# 2PLUS_Osc_Breakout_Euro.net
KiCad netlist of a schematic drawn in EAGLE
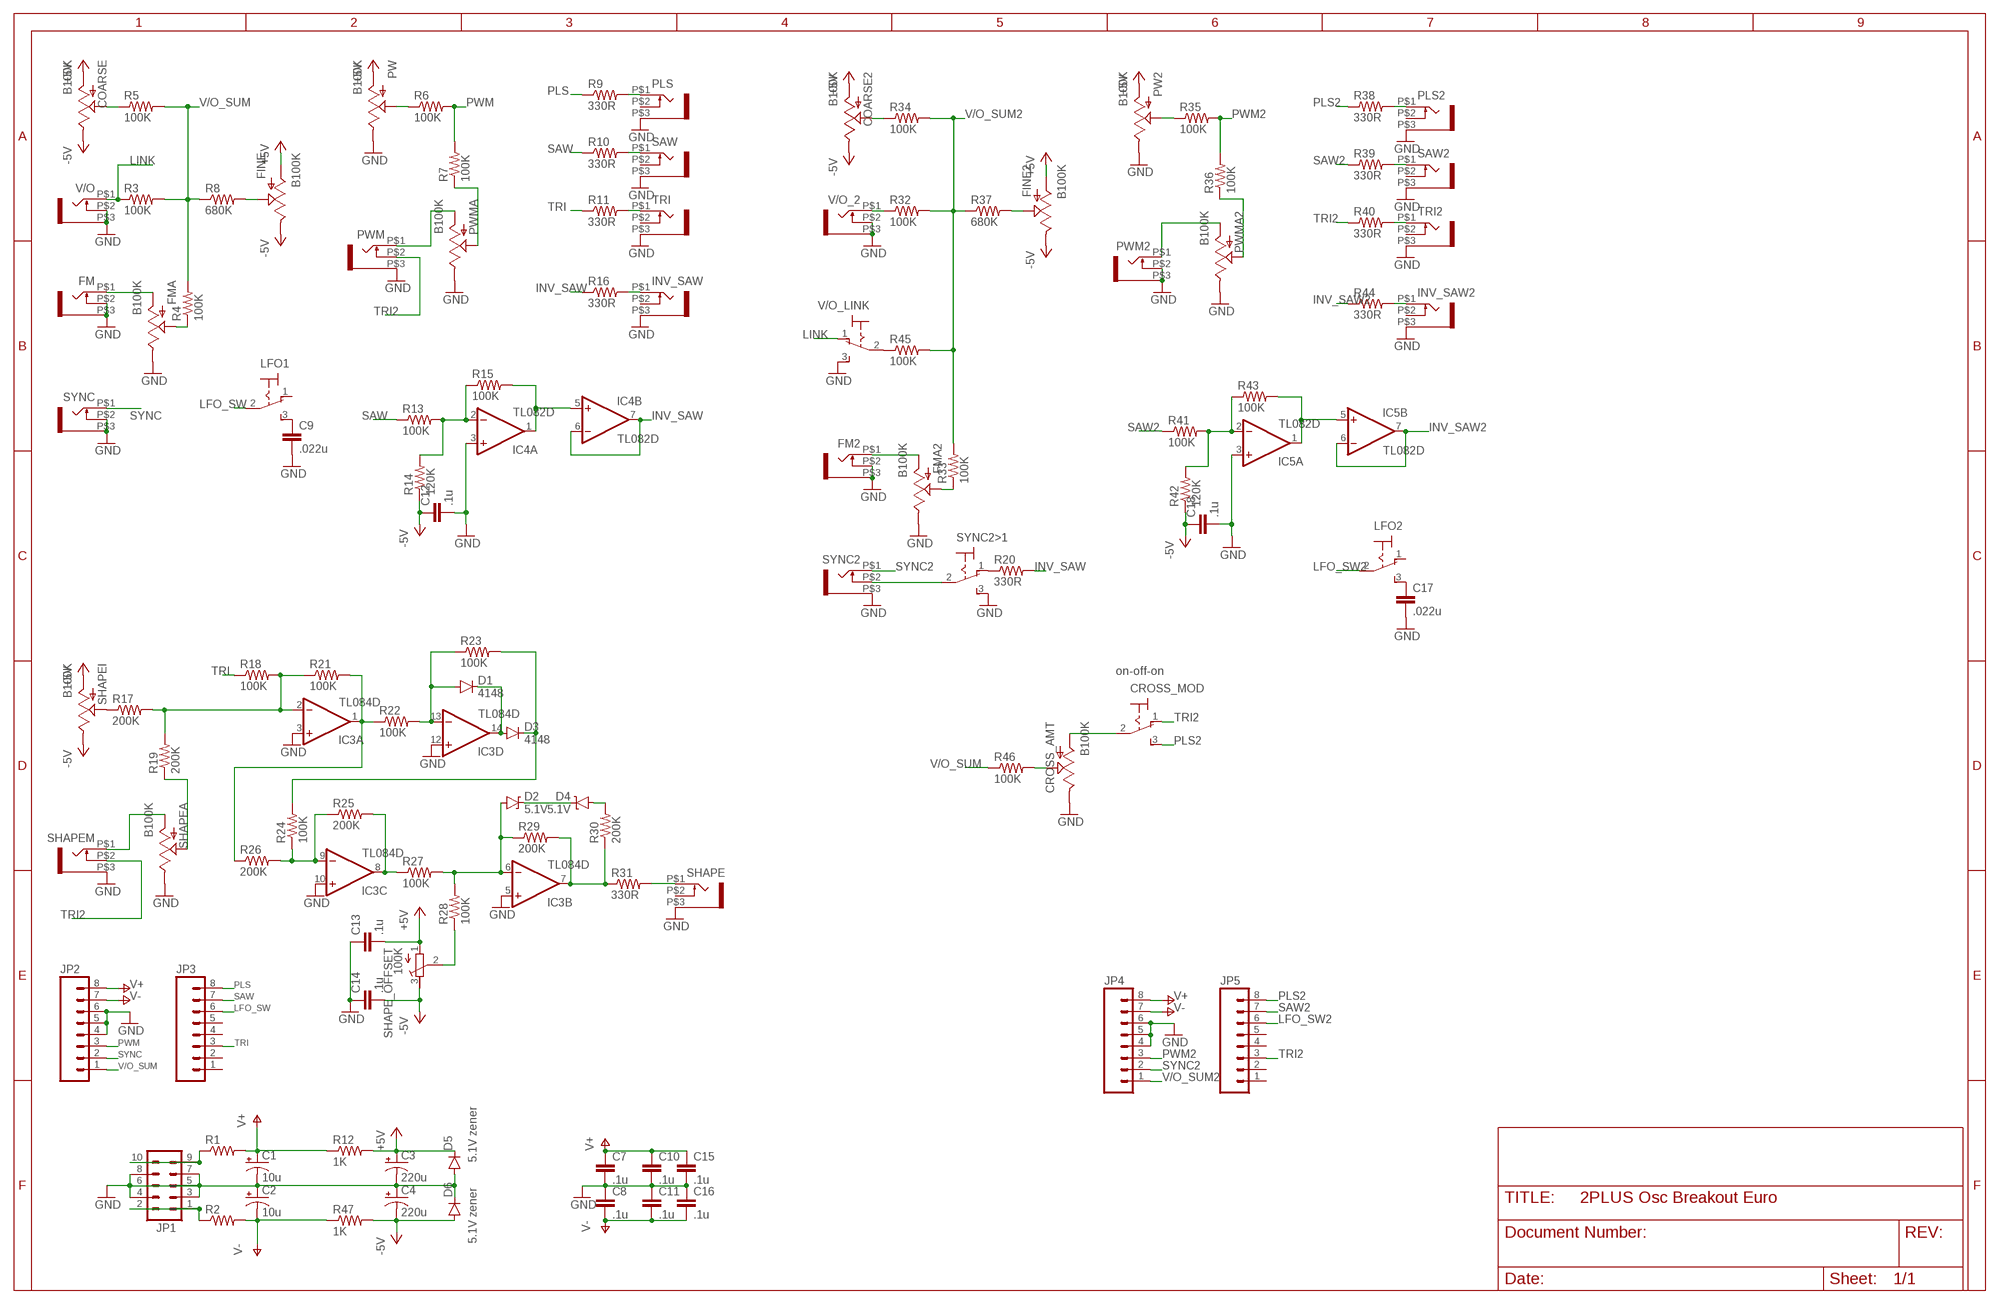
[diagram p0: schematic, sheet 1]

(export (version "E")
  (design (tool "Eeschema 10.0.6"))
  (components
    (comp (ref "C1")
      (value "10u")
      (footprint "eagle-import:PANASONIC_C")
      (libsource (lib "eagle-import") (part "CAP_POLC"))
    )
    (comp (ref "C2")
      (value "10u")
      (footprint "eagle-import:PANASONIC_C")
      (libsource (lib "eagle-import") (part "CAP_POLC"))
    )
    (comp (ref "C3")
      (value "220u")
      (footprint "eagle-import:E2,5-5")
      (libsource (lib "eagle-import") (part "CPOL-USE2.5-5"))
    )
    (comp (ref "C4")
      (value "220u")
      (footprint "eagle-import:E2,5-5")
      (libsource (lib "eagle-import") (part "CPOL-USE2.5-5"))
    )
    (comp (ref "C7")
      (value ".1u")
      (footprint "eagle-import:0805")
      (libsource (lib "eagle-import") (part "CAP0805"))
    )
    (comp (ref "C8")
      (value ".1u")
      (footprint "eagle-import:0805")
      (libsource (lib "eagle-import") (part "CAP0805"))
    )
    (comp (ref "C9")
      (value ".022u")
      (footprint "eagle-import:0805")
      (libsource (lib "eagle-import") (part "CAP0805"))
    )
    (comp (ref "C10")
      (value ".1u")
      (footprint "eagle-import:0805")
      (libsource (lib "eagle-import") (part "CAP0805"))
    )
    (comp (ref "C11")
      (value ".1u")
      (footprint "eagle-import:0805")
      (libsource (lib "eagle-import") (part "CAP0805"))
    )
    (comp (ref "C12")
      (value ".1u")
      (footprint "eagle-import:0805")
      (libsource (lib "eagle-import") (part "CAP0805"))
    )
    (comp (ref "C13")
      (value ".1u")
      (footprint "eagle-import:0805")
      (libsource (lib "eagle-import") (part "CAP0805"))
    )
    (comp (ref "C14")
      (value ".1u")
      (footprint "eagle-import:0805")
      (libsource (lib "eagle-import") (part "CAP0805"))
    )
    (comp (ref "C15")
      (value ".1u")
      (footprint "eagle-import:0805")
      (libsource (lib "eagle-import") (part "CAP0805"))
    )
    (comp (ref "C16")
      (value ".1u")
      (footprint "eagle-import:0805")
      (libsource (lib "eagle-import") (part "CAP0805"))
    )
    (comp (ref "C17")
      (value ".022u")
      (footprint "eagle-import:0805")
      (libsource (lib "eagle-import") (part "CAP0805"))
    )
    (comp (ref "C18")
      (value ".1u")
      (footprint "eagle-import:0805")
      (libsource (lib "eagle-import") (part "CAP0805"))
    )
    (comp (ref "COARSE")
      (value "B100K")
      (footprint "eagle-import:ALPS_POT")
      (libsource (lib "eagle-import") (part "POT"))
    )
    (comp (ref "COARSE2")
      (value "B100K")
      (footprint "eagle-import:ALPS_POT")
      (libsource (lib "eagle-import") (part "POT"))
    )
    (comp (ref "CROSS_AMT")
      (value "B100K")
      (footprint "eagle-import:ALPS_POT")
      (libsource (lib "eagle-import") (part "POT"))
    )
    (comp (ref "CROSS_MOD")
      (value "M9040P")
      (footprint "eagle-import:M9040P")
      (libsource (lib "eagle-import") (part "M9040P"))
    )
    (comp (ref "D1")
      (value "4148")
      (footprint "eagle-import:SOD-123")
      (libsource (lib "eagle-import") (part "DIODESOD123"))
    )
    (comp (ref "D2")
      (value "5.1V")
      (footprint "eagle-import:SOD-123")
      (libsource (lib "eagle-import") (part "DIODE-ZENER16V"))
    )
    (comp (ref "D3")
      (value "4148")
      (footprint "eagle-import:SOD-123")
      (libsource (lib "eagle-import") (part "DIODESOD123"))
    )
    (comp (ref "D4")
      (value "5.1V")
      (footprint "eagle-import:SOD-123")
      (libsource (lib "eagle-import") (part "DIODE-ZENER16V"))
    )
    (comp (ref "D5")
      (value "5.1V zener")
      (footprint "eagle-import:SOD-123")
      (libsource (lib "eagle-import") (part "DIODESOD123"))
    )
    (comp (ref "D6")
      (value "5.1V zener")
      (footprint "eagle-import:SOD-123")
      (libsource (lib "eagle-import") (part "DIODESOD123"))
    )
    (comp (ref "FINE")
      (value "B100K")
      (footprint "eagle-import:ALPS_POT")
      (libsource (lib "eagle-import") (part "POT"))
    )
    (comp (ref "FINE2")
      (value "B100K")
      (footprint "eagle-import:ALPS_POT")
      (libsource (lib "eagle-import") (part "POT"))
    )
    (comp (ref "FM")
      (value "WQP-PJ301M-12_JACK")
      (footprint "eagle-import:WQP-PJ301M-12_JACK")
      (libsource (lib "eagle-import") (part "WQP-PJ301M-12_JACK"))
    )
    (comp (ref "FM2")
      (value "WQP-PJ301M-12_JACK")
      (footprint "eagle-import:WQP-PJ301M-12_JACK")
      (libsource (lib "eagle-import") (part "WQP-PJ301M-12_JACK"))
    )
    (comp (ref "FMA")
      (value "B100K")
      (footprint "eagle-import:ALPS_POT")
      (libsource (lib "eagle-import") (part "POT"))
    )
    (comp (ref "FMA2")
      (value "B100K")
      (footprint "eagle-import:ALPS_POT")
      (libsource (lib "eagle-import") (part "POT"))
    )
    (comp (ref "IC3")
      (value "TL084D")
      (footprint "eagle-import:SO14")
      (libsource (lib "eagle-import") (part "TL084D"))
    )
    (comp (ref "IC4")
      (value "TL082D")
      (footprint "eagle-import:SO08")
      (libsource (lib "eagle-import") (part "TL082D"))
    )
    (comp (ref "IC5")
      (value "TL082D")
      (footprint "eagle-import:SO08")
      (libsource (lib "eagle-import") (part "TL082D"))
    )
    (comp (ref "INV_SAW")
      (value "WQP-PJ301M-12_JACK")
      (footprint "eagle-import:WQP-PJ301M-12_JACK")
      (libsource (lib "eagle-import") (part "WQP-PJ301M-12_JACK"))
    )
    (comp (ref "INV_SAW2")
      (value "WQP-PJ301M-12_JACK")
      (footprint "eagle-import:WQP-PJ301M-12_JACK")
      (libsource (lib "eagle-import") (part "WQP-PJ301M-12_JACK"))
    )
    (comp (ref "JP1")
      (value "M05X2PTH")
      (footprint "eagle-import:AVR_ICSP")
      (libsource (lib "eagle-import") (part "M05X2PTH"))
    )
    (comp (ref "JP2")
      (value "M08")
      (footprint "eagle-import:1X08_ROUND")
      (libsource (lib "eagle-import") (part "M08"))
    )
    (comp (ref "JP3")
      (value "M08")
      (footprint "eagle-import:1X08_ROUND")
      (libsource (lib "eagle-import") (part "M08"))
    )
    (comp (ref "JP4")
      (value "M08")
      (footprint "eagle-import:1X08_ROUND")
      (libsource (lib "eagle-import") (part "M08"))
    )
    (comp (ref "JP5")
      (value "M08")
      (footprint "eagle-import:1X08_ROUND")
      (libsource (lib "eagle-import") (part "M08"))
    )
    (comp (ref "LFO1")
      (value "M9040P")
      (footprint "eagle-import:M9040P")
      (libsource (lib "eagle-import") (part "M9040P"))
    )
    (comp (ref "LFO2")
      (value "M9040P")
      (footprint "eagle-import:M9040P")
      (libsource (lib "eagle-import") (part "M9040P"))
    )
    (comp (ref "PLS")
      (value "WQP-PJ301M-12_JACK")
      (footprint "eagle-import:WQP-PJ301M-12_JACK")
      (libsource (lib "eagle-import") (part "WQP-PJ301M-12_JACK"))
    )
    (comp (ref "PLS2")
      (value "WQP-PJ301M-12_JACK")
      (footprint "eagle-import:WQP-PJ301M-12_JACK")
      (libsource (lib "eagle-import") (part "WQP-PJ301M-12_JACK"))
    )
    (comp (ref "PW")
      (value "B100K")
      (footprint "eagle-import:ALPS_POT")
      (libsource (lib "eagle-import") (part "POT"))
    )
    (comp (ref "PW2")
      (value "B100K")
      (footprint "eagle-import:ALPS_POT")
      (libsource (lib "eagle-import") (part "POT"))
    )
    (comp (ref "PWM")
      (value "WQP-PJ301M-12_JACK")
      (footprint "eagle-import:WQP-PJ301M-12_JACK")
      (libsource (lib "eagle-import") (part "WQP-PJ301M-12_JACK"))
    )
    (comp (ref "PWM2")
      (value "WQP-PJ301M-12_JACK")
      (footprint "eagle-import:WQP-PJ301M-12_JACK")
      (libsource (lib "eagle-import") (part "WQP-PJ301M-12_JACK"))
    )
    (comp (ref "PWMA")
      (value "B100K")
      (footprint "eagle-import:ALPS_POT")
      (libsource (lib "eagle-import") (part "POT"))
    )
    (comp (ref "PWMA2")
      (value "B100K")
      (footprint "eagle-import:ALPS_POT")
      (libsource (lib "eagle-import") (part "POT"))
    )
    (comp (ref "R1")
      (value "RESISTOR0805-RES")
      (footprint "eagle-import:0805")
      (libsource (lib "eagle-import") (part "RESISTOR0805-RES"))
    )
    (comp (ref "R2")
      (value "RESISTOR0805-RES")
      (footprint "eagle-import:0805")
      (libsource (lib "eagle-import") (part "RESISTOR0805-RES"))
    )
    (comp (ref "R3")
      (value "100K")
      (footprint "eagle-import:0805")
      (libsource (lib "eagle-import") (part "RESISTOR0805-RES"))
    )
    (comp (ref "R4")
      (value "100K")
      (footprint "eagle-import:0805")
      (libsource (lib "eagle-import") (part "RESISTOR0805-RES"))
    )
    (comp (ref "R5")
      (value "100K")
      (footprint "eagle-import:0805")
      (libsource (lib "eagle-import") (part "RESISTOR0805-RES"))
    )
    (comp (ref "R6")
      (value "100K")
      (footprint "eagle-import:0805")
      (libsource (lib "eagle-import") (part "RESISTOR0805-RES"))
    )
    (comp (ref "R7")
      (value "100K")
      (footprint "eagle-import:0805")
      (libsource (lib "eagle-import") (part "RESISTOR0805-RES"))
    )
    (comp (ref "R8")
      (value "680K")
      (footprint "eagle-import:0805")
      (libsource (lib "eagle-import") (part "RESISTOR0805-RES"))
    )
    (comp (ref "R9")
      (value "330R")
      (footprint "eagle-import:0805")
      (libsource (lib "eagle-import") (part "RESISTOR0805-RES"))
    )
    (comp (ref "R10")
      (value "330R")
      (footprint "eagle-import:0805")
      (libsource (lib "eagle-import") (part "RESISTOR0805-RES"))
    )
    (comp (ref "R11")
      (value "330R")
      (footprint "eagle-import:0805")
      (libsource (lib "eagle-import") (part "RESISTOR0805-RES"))
    )
    (comp (ref "R12")
      (value "1K")
      (footprint "eagle-import:0805")
      (libsource (lib "eagle-import") (part "RESISTOR0805-RES"))
    )
    (comp (ref "R13")
      (value "100K")
      (footprint "eagle-import:0805")
      (libsource (lib "eagle-import") (part "RESISTOR0805-RES"))
    )
    (comp (ref "R14")
      (value "120K")
      (footprint "eagle-import:0805")
      (libsource (lib "eagle-import") (part "RESISTOR0805-RES"))
    )
    (comp (ref "R15")
      (value "100K")
      (footprint "eagle-import:0805")
      (libsource (lib "eagle-import") (part "RESISTOR0805-RES"))
    )
    (comp (ref "R16")
      (value "330R")
      (footprint "eagle-import:0805")
      (libsource (lib "eagle-import") (part "RESISTOR0805-RES"))
    )
    (comp (ref "R17")
      (value "200K")
      (footprint "eagle-import:0805")
      (libsource (lib "eagle-import") (part "RESISTOR0805-RES"))
    )
    (comp (ref "R18")
      (value "100K")
      (footprint "eagle-import:0805")
      (libsource (lib "eagle-import") (part "RESISTOR0805-RES"))
    )
    (comp (ref "R19")
      (value "200K")
      (footprint "eagle-import:0805")
      (libsource (lib "eagle-import") (part "RESISTOR0805-RES"))
    )
    (comp (ref "R20")
      (value "330R")
      (footprint "eagle-import:0805")
      (libsource (lib "eagle-import") (part "RESISTOR0805-RES"))
    )
    (comp (ref "R21")
      (value "100K")
      (footprint "eagle-import:0805")
      (libsource (lib "eagle-import") (part "RESISTOR0805-RES"))
    )
    (comp (ref "R22")
      (value "100K")
      (footprint "eagle-import:0805")
      (libsource (lib "eagle-import") (part "RESISTOR0805-RES"))
    )
    (comp (ref "R23")
      (value "100K")
      (footprint "eagle-import:0805")
      (libsource (lib "eagle-import") (part "RESISTOR0805-RES"))
    )
    (comp (ref "R24")
      (value "100K")
      (footprint "eagle-import:0805")
      (libsource (lib "eagle-import") (part "RESISTOR0805-RES"))
    )
    (comp (ref "R25")
      (value "200K")
      (footprint "eagle-import:0805")
      (libsource (lib "eagle-import") (part "RESISTOR0805-RES"))
    )
    (comp (ref "R26")
      (value "200K")
      (footprint "eagle-import:0805")
      (libsource (lib "eagle-import") (part "RESISTOR0805-RES"))
    )
    (comp (ref "R27")
      (value "100K")
      (footprint "eagle-import:0805")
      (libsource (lib "eagle-import") (part "RESISTOR0805-RES"))
    )
    (comp (ref "R28")
      (value "100K")
      (footprint "eagle-import:0805")
      (libsource (lib "eagle-import") (part "RESISTOR0805-RES"))
    )
    (comp (ref "R29")
      (value "200K")
      (footprint "eagle-import:0805")
      (libsource (lib "eagle-import") (part "RESISTOR0805-RES"))
    )
    (comp (ref "R30")
      (value "200K")
      (footprint "eagle-import:0805")
      (libsource (lib "eagle-import") (part "RESISTOR0805-RES"))
    )
    (comp (ref "R31")
      (value "330R")
      (footprint "eagle-import:0805")
      (libsource (lib "eagle-import") (part "RESISTOR0805-RES"))
    )
    (comp (ref "R32")
      (value "100K")
      (footprint "eagle-import:0805")
      (libsource (lib "eagle-import") (part "RESISTOR0805-RES"))
    )
    (comp (ref "R33")
      (value "100K")
      (footprint "eagle-import:0805")
      (libsource (lib "eagle-import") (part "RESISTOR0805-RES"))
    )
    (comp (ref "R34")
      (value "100K")
      (footprint "eagle-import:0805")
      (libsource (lib "eagle-import") (part "RESISTOR0805-RES"))
    )
    (comp (ref "R35")
      (value "100K")
      (footprint "eagle-import:0805")
      (libsource (lib "eagle-import") (part "RESISTOR0805-RES"))
    )
    (comp (ref "R36")
      (value "100K")
      (footprint "eagle-import:0805")
      (libsource (lib "eagle-import") (part "RESISTOR0805-RES"))
    )
    (comp (ref "R37")
      (value "680K")
      (footprint "eagle-import:0805")
      (libsource (lib "eagle-import") (part "RESISTOR0805-RES"))
    )
    (comp (ref "R38")
      (value "330R")
      (footprint "eagle-import:0805")
      (libsource (lib "eagle-import") (part "RESISTOR0805-RES"))
    )
    (comp (ref "R39")
      (value "330R")
      (footprint "eagle-import:0805")
      (libsource (lib "eagle-import") (part "RESISTOR0805-RES"))
    )
    (comp (ref "R40")
      (value "330R")
      (footprint "eagle-import:0805")
      (libsource (lib "eagle-import") (part "RESISTOR0805-RES"))
    )
    (comp (ref "R41")
      (value "100K")
      (footprint "eagle-import:0805")
      (libsource (lib "eagle-import") (part "RESISTOR0805-RES"))
    )
    (comp (ref "R42")
      (value "120K")
      (footprint "eagle-import:0805")
      (libsource (lib "eagle-import") (part "RESISTOR0805-RES"))
    )
    (comp (ref "R43")
      (value "100K")
      (footprint "eagle-import:0805")
      (libsource (lib "eagle-import") (part "RESISTOR0805-RES"))
    )
    (comp (ref "R44")
      (value "330R")
      (footprint "eagle-import:0805")
      (libsource (lib "eagle-import") (part "RESISTOR0805-RES"))
    )
    (comp (ref "R45")
      (value "100K")
      (footprint "eagle-import:0805")
      (libsource (lib "eagle-import") (part "RESISTOR0805-RES"))
    )
    (comp (ref "R46")
      (value "100K")
      (footprint "eagle-import:0805")
      (libsource (lib "eagle-import") (part "RESISTOR0805-RES"))
    )
    (comp (ref "R47")
      (value "1K")
      (footprint "eagle-import:0805")
      (libsource (lib "eagle-import") (part "RESISTOR0805-RES"))
    )
    (comp (ref "SAW")
      (value "WQP-PJ301M-12_JACK")
      (footprint "eagle-import:WQP-PJ301M-12_JACK")
      (libsource (lib "eagle-import") (part "WQP-PJ301M-12_JACK"))
    )
    (comp (ref "SAW2")
      (value "WQP-PJ301M-12_JACK")
      (footprint "eagle-import:WQP-PJ301M-12_JACK")
      (libsource (lib "eagle-import") (part "WQP-PJ301M-12_JACK"))
    )
    (comp (ref "SHAPE")
      (value "WQP-PJ301M-12_JACK")
      (footprint "eagle-import:WQP-PJ301M-12_JACK")
      (libsource (lib "eagle-import") (part "WQP-PJ301M-12_JACK"))
    )
    (comp (ref "SHAPEA")
      (value "B100K")
      (footprint "eagle-import:ALPS_POT")
      (libsource (lib "eagle-import") (part "POT"))
    )
    (comp (ref "SHAPEI")
      (value "B100K")
      (footprint "eagle-import:ALPS_POT")
      (libsource (lib "eagle-import") (part "POT"))
    )
    (comp (ref "SHAPEM")
      (value "WQP-PJ301M-12_JACK")
      (footprint "eagle-import:WQP-PJ301M-12_JACK")
      (libsource (lib "eagle-import") (part "WQP-PJ301M-12_JACK"))
    )
    (comp (ref "SHAPE_OFFSET")
      (value "100K")
      (footprint "eagle-import:RTRIM3296Y")
      (libsource (lib "eagle-import") (part "R-TRIMM3296Y"))
    )
    (comp (ref "SYNC")
      (value "WQP-PJ301M-12_JACK")
      (footprint "eagle-import:WQP-PJ301M-12_JACK")
      (libsource (lib "eagle-import") (part "WQP-PJ301M-12_JACK"))
    )
    (comp (ref "SYNC2")
      (value "WQP-PJ301M-12_JACK")
      (footprint "eagle-import:WQP-PJ301M-12_JACK")
      (libsource (lib "eagle-import") (part "WQP-PJ301M-12_JACK"))
    )
    (comp (ref "SYNC2>1")
      (value "M9040P")
      (footprint "eagle-import:M9040P")
      (libsource (lib "eagle-import") (part "M9040P"))
    )
    (comp (ref "TRI")
      (value "WQP-PJ301M-12_JACK")
      (footprint "eagle-import:WQP-PJ301M-12_JACK")
      (libsource (lib "eagle-import") (part "WQP-PJ301M-12_JACK"))
    )
    (comp (ref "TRI2")
      (value "WQP-PJ301M-12_JACK")
      (footprint "eagle-import:WQP-PJ301M-12_JACK")
      (libsource (lib "eagle-import") (part "WQP-PJ301M-12_JACK"))
    )
    (comp (ref "V/O")
      (value "WQP-PJ301M-12_JACK")
      (footprint "eagle-import:WQP-PJ301M-12_JACK")
      (libsource (lib "eagle-import") (part "WQP-PJ301M-12_JACK"))
    )
    (comp (ref "V/O_2")
      (value "WQP-PJ301M-12_JACK")
      (footprint "eagle-import:WQP-PJ301M-12_JACK")
      (libsource (lib "eagle-import") (part "WQP-PJ301M-12_JACK"))
    )
    (comp (ref "V/O_LINK")
      (value "M9040P")
      (footprint "eagle-import:M9040P")
      (libsource (lib "eagle-import") (part "M9040P"))
    )
  )
  (nets
    (net (code "1") (name "+5V") (class "Default")
      (node (ref "C13") (pin "2") (pinfunction "2_2") (pintype "passive"))
      (node (ref "C3") (pin "+") (pinfunction "+_+") (pintype "passive"))
      (node (ref "COARSE") (pin "P$3") (pinfunction "A_P$3") (pintype "passive"))
      (node (ref "COARSE2") (pin "P$3") (pinfunction "A_P$3") (pintype "passive"))
      (node (ref "D5") (pin "C") (pinfunction "C_C") (pintype "passive"))
      (node (ref "FINE") (pin "P$3") (pinfunction "A_P$3") (pintype "passive"))
      (node (ref "FINE2") (pin "P$3") (pinfunction "A_P$3") (pintype "passive"))
      (node (ref "PW") (pin "P$3") (pinfunction "A_P$3") (pintype "passive"))
      (node (ref "PW2") (pin "P$3") (pinfunction "A_P$3") (pintype "passive"))
      (node (ref "R12") (pin "2") (pinfunction "2_2") (pintype "passive"))
      (node (ref "SHAPEI") (pin "P$3") (pinfunction "A_P$3") (pintype "passive"))
      (node (ref "SHAPE_OFFSET") (pin "1") (pinfunction "A_1") (pintype "passive"))
    )
    (net (code "2") (name "-5V") (class "Default")
      (node (ref "C12") (pin "1") (pinfunction "1_1") (pintype "passive"))
      (node (ref "C14") (pin "2") (pinfunction "2_2") (pintype "passive"))
      (node (ref "C18") (pin "1") (pinfunction "1_1") (pintype "passive"))
      (node (ref "C4") (pin "-") (pinfunction "-_-") (pintype "passive"))
      (node (ref "COARSE") (pin "P$1") (pinfunction "E_P$1") (pintype "passive"))
      (node (ref "COARSE2") (pin "P$1") (pinfunction "E_P$1") (pintype "passive"))
      (node (ref "D6") (pin "A") (pinfunction "A_A") (pintype "passive"))
      (node (ref "FINE") (pin "P$1") (pinfunction "E_P$1") (pintype "passive"))
      (node (ref "FINE2") (pin "P$1") (pinfunction "E_P$1") (pintype "passive"))
      (node (ref "R14") (pin "1") (pinfunction "1_1") (pintype "passive"))
      (node (ref "R42") (pin "1") (pinfunction "1_1") (pintype "passive"))
      (node (ref "R47") (pin "2") (pinfunction "2_2") (pintype "passive"))
      (node (ref "SHAPEI") (pin "P$1") (pinfunction "E_P$1") (pintype "passive"))
      (node (ref "SHAPE_OFFSET") (pin "3") (pinfunction "E_3") (pintype "passive"))
    )
    (net (code "3") (name "/INV_SAW") (class "Default")
      (node (ref "IC4") (pin "6") (pinfunction "-IN_6") (pintype "input"))
      (node (ref "IC4") (pin "7") (pinfunction "OUT_7") (pintype "output"))
      (node (ref "R16") (pin "1") (pinfunction "1_1") (pintype "passive"))
      (node (ref "R20") (pin "2") (pinfunction "2_2") (pintype "passive"))
    )
    (net (code "4") (name "/INV_SAW2") (class "Default")
      (node (ref "IC5") (pin "6") (pinfunction "-IN_6") (pintype "input"))
      (node (ref "IC5") (pin "7") (pinfunction "OUT_7") (pintype "output"))
      (node (ref "R44") (pin "1") (pinfunction "1_1") (pintype "passive"))
    )
    (net (code "5") (name "/LFO_SW") (class "Default")
      (node (ref "JP3") (pin "6") (pinfunction "6_6") (pintype "passive"))
      (node (ref "LFO1") (pin "2") (pinfunction "P_2") (pintype "passive"))
    )
    (net (code "6") (name "/LFO_SW2") (class "Default")
      (node (ref "JP5") (pin "6") (pinfunction "6_6") (pintype "passive"))
      (node (ref "LFO2") (pin "2") (pinfunction "P_2") (pintype "passive"))
    )
    (net (code "7") (name "/LINK") (class "Default")
      (node (ref "R3") (pin "1") (pinfunction "1_1") (pintype "passive"))
      (node (ref "V/O") (pin "P$1") (pinfunction "2_P$1") (pintype "passive"))
      (node (ref "V/O_LINK") (pin "1") (pinfunction "O_1") (pintype "passive"))
    )
    (net (code "8") (name "/PLS") (class "Default")
      (node (ref "JP3") (pin "8") (pinfunction "8_8") (pintype "passive"))
      (node (ref "R9") (pin "1") (pinfunction "1_1") (pintype "passive"))
    )
    (net (code "9") (name "/PLS2") (class "Default")
      (node (ref "CROSS_MOD") (pin "3") (pinfunction "S_3") (pintype "passive"))
      (node (ref "JP5") (pin "8") (pinfunction "8_8") (pintype "passive"))
      (node (ref "R38") (pin "1") (pinfunction "1_1") (pintype "passive"))
    )
    (net (code "10") (name "/PWM") (class "Default")
      (node (ref "JP2") (pin "3") (pinfunction "3_3") (pintype "passive"))
      (node (ref "R6") (pin "2") (pinfunction "2_2") (pintype "passive"))
      (node (ref "R7") (pin "2") (pinfunction "2_2") (pintype "passive"))
    )
    (net (code "11") (name "/PWM2") (class "Default")
      (node (ref "JP4") (pin "3") (pinfunction "3_3") (pintype "passive"))
      (node (ref "R35") (pin "2") (pinfunction "2_2") (pintype "passive"))
      (node (ref "R36") (pin "2") (pinfunction "2_2") (pintype "passive"))
    )
    (net (code "12") (name "/SAW") (class "Default")
      (node (ref "JP3") (pin "7") (pinfunction "7_7") (pintype "passive"))
      (node (ref "R10") (pin "1") (pinfunction "1_1") (pintype "passive"))
      (node (ref "R13") (pin "1") (pinfunction "1_1") (pintype "passive"))
    )
    (net (code "13") (name "/SAW2") (class "Default")
      (node (ref "JP5") (pin "7") (pinfunction "7_7") (pintype "passive"))
      (node (ref "R39") (pin "1") (pinfunction "1_1") (pintype "passive"))
      (node (ref "R41") (pin "1") (pinfunction "1_1") (pintype "passive"))
    )
    (net (code "14") (name "/SYNC") (class "Default")
      (node (ref "JP2") (pin "2") (pinfunction "2_2") (pintype "passive"))
      (node (ref "SYNC") (pin "P$1") (pinfunction "2_P$1") (pintype "passive"))
    )
    (net (code "15") (name "/SYNC2") (class "Default")
      (node (ref "JP4") (pin "2") (pinfunction "2_2") (pintype "passive"))
      (node (ref "SYNC2") (pin "P$1") (pinfunction "2_P$1") (pintype "passive"))
    )
    (net (code "16") (name "/TRI") (class "Default")
      (node (ref "JP3") (pin "3") (pinfunction "3_3") (pintype "passive"))
      (node (ref "R11") (pin "1") (pinfunction "1_1") (pintype "passive"))
      (node (ref "R18") (pin "1") (pinfunction "1_1") (pintype "passive"))
    )
    (net (code "17") (name "/TRI2") (class "Default")
      (node (ref "CROSS_MOD") (pin "1") (pinfunction "O_1") (pintype "passive"))
      (node (ref "JP5") (pin "3") (pinfunction "3_3") (pintype "passive"))
      (node (ref "PWM") (pin "P$2") (pinfunction "3_P$2") (pintype "passive"))
      (node (ref "R40") (pin "1") (pinfunction "1_1") (pintype "passive"))
      (node (ref "SHAPEM") (pin "P$2") (pinfunction "3_P$2") (pintype "passive"))
    )
    (net (code "18") (name "/V{slash}O_SUM") (class "Default")
      (node (ref "JP2") (pin "1") (pinfunction "1_1") (pintype "passive"))
      (node (ref "R3") (pin "2") (pinfunction "2_2") (pintype "passive"))
      (node (ref "R4") (pin "2") (pinfunction "2_2") (pintype "passive"))
      (node (ref "R46") (pin "1") (pinfunction "1_1") (pintype "passive"))
      (node (ref "R5") (pin "2") (pinfunction "2_2") (pintype "passive"))
      (node (ref "R8") (pin "1") (pinfunction "1_1") (pintype "passive"))
    )
    (net (code "19") (name "/V{slash}O_SUM2") (class "Default")
      (node (ref "JP4") (pin "1") (pinfunction "1_1") (pintype "passive"))
      (node (ref "R32") (pin "2") (pinfunction "2_2") (pintype "passive"))
      (node (ref "R33") (pin "2") (pinfunction "2_2") (pintype "passive"))
      (node (ref "R34") (pin "2") (pinfunction "2_2") (pintype "passive"))
      (node (ref "R37") (pin "1") (pinfunction "1_1") (pintype "passive"))
      (node (ref "R45") (pin "2") (pinfunction "2_2") (pintype "passive"))
    )
    (net (code "20") (name "GND") (class "Default")
      (node (ref "C1") (pin "-") (pinfunction "-_-") (pintype "passive"))
      (node (ref "C10") (pin "2") (pinfunction "2_2") (pintype "passive"))
      (node (ref "C11") (pin "1") (pinfunction "1_1") (pintype "passive"))
      (node (ref "C12") (pin "2") (pinfunction "2_2") (pintype "passive"))
      (node (ref "C13") (pin "1") (pinfunction "1_1") (pintype "passive"))
      (node (ref "C14") (pin "1") (pinfunction "1_1") (pintype "passive"))
      (node (ref "C15") (pin "2") (pinfunction "2_2") (pintype "passive"))
      (node (ref "C16") (pin "1") (pinfunction "1_1") (pintype "passive"))
      (node (ref "C17") (pin "2") (pinfunction "2_2") (pintype "passive"))
      (node (ref "C18") (pin "2") (pinfunction "2_2") (pintype "passive"))
      (node (ref "C2") (pin "+") (pinfunction "+_+") (pintype "passive"))
      (node (ref "C3") (pin "-") (pinfunction "-_-") (pintype "passive"))
      (node (ref "C4") (pin "+") (pinfunction "+_+") (pintype "passive"))
      (node (ref "C7") (pin "2") (pinfunction "2_2") (pintype "passive"))
      (node (ref "C8") (pin "1") (pinfunction "1_1") (pintype "passive"))
      (node (ref "C9") (pin "2") (pinfunction "2_2") (pintype "passive"))
      (node (ref "CROSS_AMT") (pin "P$1") (pinfunction "E_P$1") (pintype "passive"))
      (node (ref "D5") (pin "A") (pinfunction "A_A") (pintype "passive"))
      (node (ref "D6") (pin "C") (pinfunction "C_C") (pintype "passive"))
      (node (ref "FM") (pin "P$2") (pinfunction "3_P$2") (pintype "passive"))
      (node (ref "FM") (pin "P$3") (pinfunction "1_P$3") (pintype "passive"))
      (node (ref "FM2") (pin "P$2") (pinfunction "3_P$2") (pintype "passive"))
      (node (ref "FM2") (pin "P$3") (pinfunction "1_P$3") (pintype "passive"))
      (node (ref "FMA") (pin "P$1") (pinfunction "E_P$1") (pintype "passive"))
      (node (ref "FMA2") (pin "P$1") (pinfunction "E_P$1") (pintype "passive"))
      (node (ref "IC3") (pin "10") (pinfunction "+IN_10") (pintype "input"))
      (node (ref "IC3") (pin "12") (pinfunction "+IN_12") (pintype "input"))
      (node (ref "IC3") (pin "3") (pinfunction "+IN_3") (pintype "input"))
      (node (ref "IC3") (pin "5") (pinfunction "+IN_5") (pintype "input"))
      (node (ref "IC4") (pin "3") (pinfunction "+IN_3") (pintype "input"))
      (node (ref "IC5") (pin "3") (pinfunction "+IN_3") (pintype "input"))
      (node (ref "INV_SAW") (pin "P$3") (pinfunction "1_P$3") (pintype "passive"))
      (node (ref "INV_SAW2") (pin "P$3") (pinfunction "1_P$3") (pintype "passive"))
      (node (ref "JP1") (pin "3") (pinfunction "3_3") (pintype "passive"))
      (node (ref "JP1") (pin "4") (pinfunction "4_4") (pintype "passive"))
      (node (ref "JP1") (pin "5") (pinfunction "5_5") (pintype "passive"))
      (node (ref "JP1") (pin "6") (pinfunction "6_6") (pintype "passive"))
      (node (ref "JP1") (pin "7") (pinfunction "7_7") (pintype "passive"))
      (node (ref "JP1") (pin "8") (pinfunction "8_8") (pintype "passive"))
      (node (ref "JP2") (pin "4") (pinfunction "4_4") (pintype "passive"))
      (node (ref "JP2") (pin "5") (pinfunction "5_5") (pintype "passive"))
      (node (ref "JP2") (pin "6") (pinfunction "6_6") (pintype "passive"))
      (node (ref "JP4") (pin "4") (pinfunction "4_4") (pintype "passive"))
      (node (ref "JP4") (pin "5") (pinfunction "5_5") (pintype "passive"))
      (node (ref "JP4") (pin "6") (pinfunction "6_6") (pintype "passive"))
      (node (ref "PLS") (pin "P$3") (pinfunction "1_P$3") (pintype "passive"))
      (node (ref "PLS2") (pin "P$3") (pinfunction "1_P$3") (pintype "passive"))
      (node (ref "PW") (pin "P$1") (pinfunction "E_P$1") (pintype "passive"))
      (node (ref "PW2") (pin "P$1") (pinfunction "E_P$1") (pintype "passive"))
      (node (ref "PWM") (pin "P$3") (pinfunction "1_P$3") (pintype "passive"))
      (node (ref "PWM2") (pin "P$2") (pinfunction "3_P$2") (pintype "passive"))
      (node (ref "PWM2") (pin "P$3") (pinfunction "1_P$3") (pintype "passive"))
      (node (ref "PWMA") (pin "P$1") (pinfunction "E_P$1") (pintype "passive"))
      (node (ref "PWMA2") (pin "P$1") (pinfunction "E_P$1") (pintype "passive"))
      (node (ref "SAW") (pin "P$3") (pinfunction "1_P$3") (pintype "passive"))
      (node (ref "SAW2") (pin "P$3") (pinfunction "1_P$3") (pintype "passive"))
      (node (ref "SHAPE") (pin "P$3") (pinfunction "1_P$3") (pintype "passive"))
      (node (ref "SHAPEA") (pin "P$1") (pinfunction "E_P$1") (pintype "passive"))
      (node (ref "SHAPEM") (pin "P$3") (pinfunction "1_P$3") (pintype "passive"))
      (node (ref "SYNC") (pin "P$2") (pinfunction "3_P$2") (pintype "passive"))
      (node (ref "SYNC") (pin "P$3") (pinfunction "1_P$3") (pintype "passive"))
      (node (ref "SYNC2") (pin "P$3") (pinfunction "1_P$3") (pintype "passive"))
      (node (ref "SYNC2>1") (pin "3") (pinfunction "S_3") (pintype "passive"))
      (node (ref "TRI") (pin "P$3") (pinfunction "1_P$3") (pintype "passive"))
      (node (ref "TRI2") (pin "P$3") (pinfunction "1_P$3") (pintype "passive"))
      (node (ref "V/O") (pin "P$2") (pinfunction "3_P$2") (pintype "passive"))
      (node (ref "V/O") (pin "P$3") (pinfunction "1_P$3") (pintype "passive"))
      (node (ref "V/O_2") (pin "P$2") (pinfunction "3_P$2") (pintype "passive"))
      (node (ref "V/O_2") (pin "P$3") (pinfunction "1_P$3") (pintype "passive"))
      (node (ref "V/O_LINK") (pin "3") (pinfunction "S_3") (pintype "passive"))
    )
    (net (code "21") (name "Net-(COARSE-S)") (class "Default")
      (node (ref "COARSE") (pin "P$2") (pinfunction "S_P$2") (pintype "passive"))
      (node (ref "R5") (pin "1") (pinfunction "1_1") (pintype "passive"))
    )
    (net (code "22") (name "Net-(COARSE2-S)") (class "Default")
      (node (ref "COARSE2") (pin "P$2") (pinfunction "S_P$2") (pintype "passive"))
      (node (ref "R34") (pin "1") (pinfunction "1_1") (pintype "passive"))
    )
    (net (code "23") (name "Net-(CROSS_AMT-A)") (class "Default")
      (node (ref "CROSS_AMT") (pin "P$3") (pinfunction "A_P$3") (pintype "passive"))
      (node (ref "CROSS_MOD") (pin "2") (pinfunction "P_2") (pintype "passive"))
    )
    (net (code "24") (name "Net-(CROSS_AMT-S)") (class "Default")
      (node (ref "CROSS_AMT") (pin "P$2") (pinfunction "S_P$2") (pintype "passive"))
      (node (ref "R46") (pin "2") (pinfunction "2_2") (pintype "passive"))
    )
    (net (code "25") (name "Net-(D2-PadC)") (class "Default")
      (node (ref "D2") (pin "C") (pinfunction "C_C") (pintype "passive"))
      (node (ref "D4") (pin "C") (pinfunction "C_C") (pintype "passive"))
    )
    (net (code "26") (name "Net-(D3-PadC)") (class "Default")
      (node (ref "D3") (pin "C") (pinfunction "C_C") (pintype "passive"))
      (node (ref "R23") (pin "2") (pinfunction "2_2") (pintype "passive"))
      (node (ref "R24") (pin "2") (pinfunction "2_2") (pintype "passive"))
    )
    (net (code "27") (name "Net-(D4-PadA)") (class "Default")
      (node (ref "D4") (pin "A") (pinfunction "A_A") (pintype "passive"))
      (node (ref "R30") (pin "2") (pinfunction "2_2") (pintype "passive"))
    )
    (net (code "28") (name "Net-(FINE-S)") (class "Default")
      (node (ref "FINE") (pin "P$2") (pinfunction "S_P$2") (pintype "passive"))
      (node (ref "R8") (pin "2") (pinfunction "2_2") (pintype "passive"))
    )
    (net (code "29") (name "Net-(FINE2-S)") (class "Default")
      (node (ref "FINE2") (pin "P$2") (pinfunction "S_P$2") (pintype "passive"))
      (node (ref "R37") (pin "2") (pinfunction "2_2") (pintype "passive"))
    )
    (net (code "30") (name "Net-(FM-2)") (class "Default")
      (node (ref "FM") (pin "P$1") (pinfunction "2_P$1") (pintype "passive"))
      (node (ref "FMA") (pin "P$3") (pinfunction "A_P$3") (pintype "passive"))
    )
    (net (code "31") (name "Net-(FM2-2)") (class "Default")
      (node (ref "FM2") (pin "P$1") (pinfunction "2_P$1") (pintype "passive"))
      (node (ref "FMA2") (pin "P$3") (pinfunction "A_P$3") (pintype "passive"))
    )
    (net (code "32") (name "Net-(FMA-S)") (class "Default")
      (node (ref "FMA") (pin "P$2") (pinfunction "S_P$2") (pintype "passive"))
      (node (ref "R4") (pin "1") (pinfunction "1_1") (pintype "passive"))
    )
    (net (code "33") (name "Net-(FMA2-S)") (class "Default")
      (node (ref "FMA2") (pin "P$2") (pinfunction "S_P$2") (pintype "passive"))
      (node (ref "R33") (pin "1") (pinfunction "1_1") (pintype "passive"))
    )
    (net (code "34") (name "Net-(IC3A--IN)") (class "Default")
      (node (ref "IC3") (pin "2") (pinfunction "-IN_2") (pintype "input"))
      (node (ref "R17") (pin "2") (pinfunction "2_2") (pintype "passive"))
      (node (ref "R18") (pin "2") (pinfunction "2_2") (pintype "passive"))
      (node (ref "R19") (pin "2") (pinfunction "2_2") (pintype "passive"))
      (node (ref "R21") (pin "1") (pinfunction "1_1") (pintype "passive"))
    )
    (net (code "35") (name "Net-(IC3A-OUT)") (class "Default")
      (node (ref "IC3") (pin "1") (pinfunction "OUT_1") (pintype "output"))
      (node (ref "R21") (pin "2") (pinfunction "2_2") (pintype "passive"))
      (node (ref "R22") (pin "1") (pinfunction "1_1") (pintype "passive"))
      (node (ref "R26") (pin "1") (pinfunction "1_1") (pintype "passive"))
    )
    (net (code "36") (name "Net-(IC3B--IN)") (class "Default")
      (node (ref "D2") (pin "A") (pinfunction "A_A") (pintype "passive"))
      (node (ref "IC3") (pin "6") (pinfunction "-IN_6") (pintype "input"))
      (node (ref "R27") (pin "2") (pinfunction "2_2") (pintype "passive"))
      (node (ref "R28") (pin "2") (pinfunction "2_2") (pintype "passive"))
      (node (ref "R29") (pin "1") (pinfunction "1_1") (pintype "passive"))
    )
    (net (code "37") (name "Net-(IC3B-OUT)") (class "Default")
      (node (ref "IC3") (pin "7") (pinfunction "OUT_7") (pintype "output"))
      (node (ref "R29") (pin "2") (pinfunction "2_2") (pintype "passive"))
      (node (ref "R30") (pin "1") (pinfunction "1_1") (pintype "passive"))
      (node (ref "R31") (pin "1") (pinfunction "1_1") (pintype "passive"))
    )
    (net (code "38") (name "Net-(IC3C--IN)") (class "Default")
      (node (ref "IC3") (pin "9") (pinfunction "-IN_9") (pintype "input"))
      (node (ref "R24") (pin "1") (pinfunction "1_1") (pintype "passive"))
      (node (ref "R25") (pin "1") (pinfunction "1_1") (pintype "passive"))
      (node (ref "R26") (pin "2") (pinfunction "2_2") (pintype "passive"))
    )
    (net (code "39") (name "Net-(IC3C-OUT)") (class "Default")
      (node (ref "IC3") (pin "8") (pinfunction "OUT_8") (pintype "output"))
      (node (ref "R25") (pin "2") (pinfunction "2_2") (pintype "passive"))
      (node (ref "R27") (pin "1") (pinfunction "1_1") (pintype "passive"))
    )
    (net (code "40") (name "Net-(IC3D--IN)") (class "Default")
      (node (ref "D1") (pin "A") (pinfunction "A_A") (pintype "passive"))
      (node (ref "IC3") (pin "13") (pinfunction "-IN_13") (pintype "input"))
      (node (ref "R22") (pin "2") (pinfunction "2_2") (pintype "passive"))
      (node (ref "R23") (pin "1") (pinfunction "1_1") (pintype "passive"))
    )
    (net (code "41") (name "Net-(IC3D-OUT)") (class "Default")
      (node (ref "D1") (pin "C") (pinfunction "C_C") (pintype "passive"))
      (node (ref "D3") (pin "A") (pinfunction "A_A") (pintype "passive"))
      (node (ref "IC3") (pin "14") (pinfunction "OUT_14") (pintype "output"))
    )
    (net (code "42") (name "Net-(IC4A--IN)") (class "Default")
      (node (ref "IC4") (pin "2") (pinfunction "-IN_2") (pintype "input"))
      (node (ref "R13") (pin "2") (pinfunction "2_2") (pintype "passive"))
      (node (ref "R14") (pin "2") (pinfunction "2_2") (pintype "passive"))
      (node (ref "R15") (pin "1") (pinfunction "1_1") (pintype "passive"))
    )
    (net (code "43") (name "Net-(IC4A-OUT)") (class "Default")
      (node (ref "IC4") (pin "1") (pinfunction "OUT_1") (pintype "output"))
      (node (ref "IC4") (pin "5") (pinfunction "+IN_5") (pintype "input"))
      (node (ref "R15") (pin "2") (pinfunction "2_2") (pintype "passive"))
    )
    (net (code "44") (name "Net-(IC5A--IN)") (class "Default")
      (node (ref "IC5") (pin "2") (pinfunction "-IN_2") (pintype "input"))
      (node (ref "R41") (pin "2") (pinfunction "2_2") (pintype "passive"))
      (node (ref "R42") (pin "2") (pinfunction "2_2") (pintype "passive"))
      (node (ref "R43") (pin "1") (pinfunction "1_1") (pintype "passive"))
    )
    (net (code "45") (name "Net-(IC5A-OUT)") (class "Default")
      (node (ref "IC5") (pin "1") (pinfunction "OUT_1") (pintype "output"))
      (node (ref "IC5") (pin "5") (pinfunction "+IN_5") (pintype "input"))
      (node (ref "R43") (pin "2") (pinfunction "2_2") (pintype "passive"))
    )
    (net (code "46") (name "Net-(INV_SAW-2)") (class "Default")
      (node (ref "INV_SAW") (pin "P$1") (pinfunction "2_P$1") (pintype "passive"))
      (node (ref "R16") (pin "2") (pinfunction "2_2") (pintype "passive"))
    )
    (net (code "47") (name "Net-(INV_SAW2-2)") (class "Default")
      (node (ref "INV_SAW2") (pin "P$1") (pinfunction "2_P$1") (pintype "passive"))
      (node (ref "R44") (pin "2") (pinfunction "2_2") (pintype "passive"))
    )
    (net (code "48") (name "Net-(JP1-Pad1)") (class "Default")
      (node (ref "JP1") (pin "1") (pinfunction "1_1") (pintype "passive"))
      (node (ref "JP1") (pin "2") (pinfunction "2_2") (pintype "passive"))
      (node (ref "R2") (pin "1") (pinfunction "1_1") (pintype "passive"))
    )
    (net (code "49") (name "Net-(JP1-Pad10)") (class "Default")
      (node (ref "JP1") (pin "10") (pinfunction "10_10") (pintype "passive"))
      (node (ref "JP1") (pin "9") (pinfunction "9_9") (pintype "passive"))
      (node (ref "R1") (pin "1") (pinfunction "1_1") (pintype "passive"))
    )
    (net (code "50") (name "Net-(LFO1-S)") (class "Default")
      (node (ref "C9") (pin "1") (pinfunction "1_1") (pintype "passive"))
      (node (ref "LFO1") (pin "3") (pinfunction "S_3") (pintype "passive"))
    )
    (net (code "51") (name "Net-(LFO2-S)") (class "Default")
      (node (ref "C17") (pin "1") (pinfunction "1_1") (pintype "passive"))
      (node (ref "LFO2") (pin "3") (pinfunction "S_3") (pintype "passive"))
    )
    (net (code "52") (name "Net-(PLS-2)") (class "Default")
      (node (ref "PLS") (pin "P$1") (pinfunction "2_P$1") (pintype "passive"))
      (node (ref "R9") (pin "2") (pinfunction "2_2") (pintype "passive"))
    )
    (net (code "53") (name "Net-(PLS2-2)") (class "Default")
      (node (ref "PLS2") (pin "P$1") (pinfunction "2_P$1") (pintype "passive"))
      (node (ref "R38") (pin "2") (pinfunction "2_2") (pintype "passive"))
    )
    (net (code "54") (name "Net-(PW-S)") (class "Default")
      (node (ref "PW") (pin "P$2") (pinfunction "S_P$2") (pintype "passive"))
      (node (ref "R6") (pin "1") (pinfunction "1_1") (pintype "passive"))
    )
    (net (code "55") (name "Net-(PW2-S)") (class "Default")
      (node (ref "PW2") (pin "P$2") (pinfunction "S_P$2") (pintype "passive"))
      (node (ref "R35") (pin "1") (pinfunction "1_1") (pintype "passive"))
    )
    (net (code "56") (name "Net-(PWM-2)") (class "Default")
      (node (ref "PWM") (pin "P$1") (pinfunction "2_P$1") (pintype "passive"))
      (node (ref "PWMA") (pin "P$3") (pinfunction "A_P$3") (pintype "passive"))
    )
    (net (code "57") (name "Net-(PWM2-2)") (class "Default")
      (node (ref "PWM2") (pin "P$1") (pinfunction "2_P$1") (pintype "passive"))
      (node (ref "PWMA2") (pin "P$3") (pinfunction "A_P$3") (pintype "passive"))
    )
    (net (code "58") (name "Net-(PWMA-S)") (class "Default")
      (node (ref "PWMA") (pin "P$2") (pinfunction "S_P$2") (pintype "passive"))
      (node (ref "R7") (pin "1") (pinfunction "1_1") (pintype "passive"))
    )
    (net (code "59") (name "Net-(PWMA2-S)") (class "Default")
      (node (ref "PWMA2") (pin "P$2") (pinfunction "S_P$2") (pintype "passive"))
      (node (ref "R36") (pin "1") (pinfunction "1_1") (pintype "passive"))
    )
    (net (code "60") (name "Net-(SAW-2)") (class "Default")
      (node (ref "R10") (pin "2") (pinfunction "2_2") (pintype "passive"))
      (node (ref "SAW") (pin "P$1") (pinfunction "2_P$1") (pintype "passive"))
    )
    (net (code "61") (name "Net-(SAW2-2)") (class "Default")
      (node (ref "R39") (pin "2") (pinfunction "2_2") (pintype "passive"))
      (node (ref "SAW2") (pin "P$1") (pinfunction "2_P$1") (pintype "passive"))
    )
    (net (code "62") (name "Net-(SHAPE-2)") (class "Default")
      (node (ref "R31") (pin "2") (pinfunction "2_2") (pintype "passive"))
      (node (ref "SHAPE") (pin "P$1") (pinfunction "2_P$1") (pintype "passive"))
    )
    (net (code "63") (name "Net-(SHAPEA-A)") (class "Default")
      (node (ref "SHAPEA") (pin "P$3") (pinfunction "A_P$3") (pintype "passive"))
      (node (ref "SHAPEM") (pin "P$1") (pinfunction "2_P$1") (pintype "passive"))
    )
    (net (code "64") (name "Net-(SHAPEA-S)") (class "Default")
      (node (ref "R19") (pin "1") (pinfunction "1_1") (pintype "passive"))
      (node (ref "SHAPEA") (pin "P$2") (pinfunction "S_P$2") (pintype "passive"))
    )
    (net (code "65") (name "Net-(SHAPEI-S)") (class "Default")
      (node (ref "R17") (pin "1") (pinfunction "1_1") (pintype "passive"))
      (node (ref "SHAPEI") (pin "P$2") (pinfunction "S_P$2") (pintype "passive"))
    )
    (net (code "66") (name "Net-(SHAPE_OFFSET-S)") (class "Default")
      (node (ref "R28") (pin "1") (pinfunction "1_1") (pintype "passive"))
      (node (ref "SHAPE_OFFSET") (pin "2") (pinfunction "S_2") (pintype "passive"))
    )
    (net (code "67") (name "Net-(SYNC2-3)") (class "Default")
      (node (ref "SYNC2") (pin "P$2") (pinfunction "3_P$2") (pintype "passive"))
      (node (ref "SYNC2>1") (pin "2") (pinfunction "P_2") (pintype "passive"))
    )
    (net (code "68") (name "Net-(SYNC2>1-O)") (class "Default")
      (node (ref "R20") (pin "1") (pinfunction "1_1") (pintype "passive"))
      (node (ref "SYNC2>1") (pin "1") (pinfunction "O_1") (pintype "passive"))
    )
    (net (code "69") (name "Net-(TRI-2)") (class "Default")
      (node (ref "R11") (pin "2") (pinfunction "2_2") (pintype "passive"))
      (node (ref "TRI") (pin "P$1") (pinfunction "2_P$1") (pintype "passive"))
    )
    (net (code "70") (name "Net-(TRI2-2)") (class "Default")
      (node (ref "R40") (pin "2") (pinfunction "2_2") (pintype "passive"))
      (node (ref "TRI2") (pin "P$1") (pinfunction "2_P$1") (pintype "passive"))
    )
    (net (code "71") (name "Net-(V/O_2-2)") (class "Default")
      (node (ref "R32") (pin "1") (pinfunction "1_1") (pintype "passive"))
      (node (ref "V/O_2") (pin "P$1") (pinfunction "2_P$1") (pintype "passive"))
    )
    (net (code "72") (name "Net-(V/O_LINK-P)") (class "Default")
      (node (ref "R45") (pin "1") (pinfunction "1_1") (pintype "passive"))
      (node (ref "V/O_LINK") (pin "2") (pinfunction "P_2") (pintype "passive"))
    )
    (net (code "73") (name "V+") (class "Default")
      (node (ref "C1") (pin "+") (pinfunction "+_+") (pintype "passive"))
      (node (ref "C10") (pin "1") (pinfunction "1_1") (pintype "passive"))
      (node (ref "C15") (pin "1") (pinfunction "1_1") (pintype "passive"))
      (node (ref "C7") (pin "1") (pinfunction "1_1") (pintype "passive"))
      (node (ref "JP2") (pin "8") (pinfunction "8_8") (pintype "passive"))
      (node (ref "JP4") (pin "8") (pinfunction "8_8") (pintype "passive"))
      (node (ref "R1") (pin "2") (pinfunction "2_2") (pintype "passive"))
      (node (ref "R12") (pin "1") (pinfunction "1_1") (pintype "passive"))
    )
    (net (code "74") (name "V-") (class "Default")
      (node (ref "C11") (pin "2") (pinfunction "2_2") (pintype "passive"))
      (node (ref "C16") (pin "2") (pinfunction "2_2") (pintype "passive"))
      (node (ref "C2") (pin "-") (pinfunction "-_-") (pintype "passive"))
      (node (ref "C8") (pin "2") (pinfunction "2_2") (pintype "passive"))
      (node (ref "JP2") (pin "7") (pinfunction "7_7") (pintype "passive"))
      (node (ref "JP4") (pin "7") (pinfunction "7_7") (pintype "passive"))
      (node (ref "R2") (pin "2") (pinfunction "2_2") (pintype "passive"))
      (node (ref "R47") (pin "1") (pinfunction "1_1") (pintype "passive"))
    )
    (net (code "75") (name "unconnected-(INV_SAW-3-PadP$2)") (class "Default")
      (node (ref "INV_SAW") (pin "P$2") (pinfunction "3_P$2") (pintype "passive"))
    )
    (net (code "76") (name "unconnected-(INV_SAW2-3-PadP$2)") (class "Default")
      (node (ref "INV_SAW2") (pin "P$2") (pinfunction "3_P$2") (pintype "passive"))
    )
    (net (code "77") (name "unconnected-(JP3-Pad1)") (class "Default")
      (node (ref "JP3") (pin "1") (pinfunction "1_1") (pintype "passive"))
    )
    (net (code "78") (name "unconnected-(JP3-Pad2)") (class "Default")
      (node (ref "JP3") (pin "2") (pinfunction "2_2") (pintype "passive"))
    )
    (net (code "79") (name "unconnected-(JP3-Pad4)") (class "Default")
      (node (ref "JP3") (pin "4") (pinfunction "4_4") (pintype "passive"))
    )
    (net (code "80") (name "unconnected-(JP3-Pad5)") (class "Default")
      (node (ref "JP3") (pin "5") (pinfunction "5_5") (pintype "passive"))
    )
    (net (code "81") (name "unconnected-(JP5-Pad1)") (class "Default")
      (node (ref "JP5") (pin "1") (pinfunction "1_1") (pintype "passive"))
    )
    (net (code "82") (name "unconnected-(JP5-Pad2)") (class "Default")
      (node (ref "JP5") (pin "2") (pinfunction "2_2") (pintype "passive"))
    )
    (net (code "83") (name "unconnected-(JP5-Pad4)") (class "Default")
      (node (ref "JP5") (pin "4") (pinfunction "4_4") (pintype "passive"))
    )
    (net (code "84") (name "unconnected-(JP5-Pad5)") (class "Default")
      (node (ref "JP5") (pin "5") (pinfunction "5_5") (pintype "passive"))
    )
    (net (code "85") (name "unconnected-(LFO1-O-Pad1)") (class "Default")
      (node (ref "LFO1") (pin "1") (pinfunction "O_1") (pintype "passive"))
    )
    (net (code "86") (name "unconnected-(LFO2-O-Pad1)") (class "Default")
      (node (ref "LFO2") (pin "1") (pinfunction "O_1") (pintype "passive"))
    )
    (net (code "87") (name "unconnected-(PLS-3-PadP$2)") (class "Default")
      (node (ref "PLS") (pin "P$2") (pinfunction "3_P$2") (pintype "passive"))
    )
    (net (code "88") (name "unconnected-(PLS2-3-PadP$2)") (class "Default")
      (node (ref "PLS2") (pin "P$2") (pinfunction "3_P$2") (pintype "passive"))
    )
    (net (code "89") (name "unconnected-(SAW-3-PadP$2)") (class "Default")
      (node (ref "SAW") (pin "P$2") (pinfunction "3_P$2") (pintype "passive"))
    )
    (net (code "90") (name "unconnected-(SAW2-3-PadP$2)") (class "Default")
      (node (ref "SAW2") (pin "P$2") (pinfunction "3_P$2") (pintype "passive"))
    )
    (net (code "91") (name "unconnected-(SHAPE-3-PadP$2)") (class "Default")
      (node (ref "SHAPE") (pin "P$2") (pinfunction "3_P$2") (pintype "passive"))
    )
    (net (code "92") (name "unconnected-(TRI-3-PadP$2)") (class "Default")
      (node (ref "TRI") (pin "P$2") (pinfunction "3_P$2") (pintype "passive"))
    )
    (net (code "93") (name "unconnected-(TRI2-3-PadP$2)") (class "Default")
      (node (ref "TRI2") (pin "P$2") (pinfunction "3_P$2") (pintype "passive"))
    )
  )
)
